# btnsm.net
KiCad netlist of a schematic drawn in EAGLE
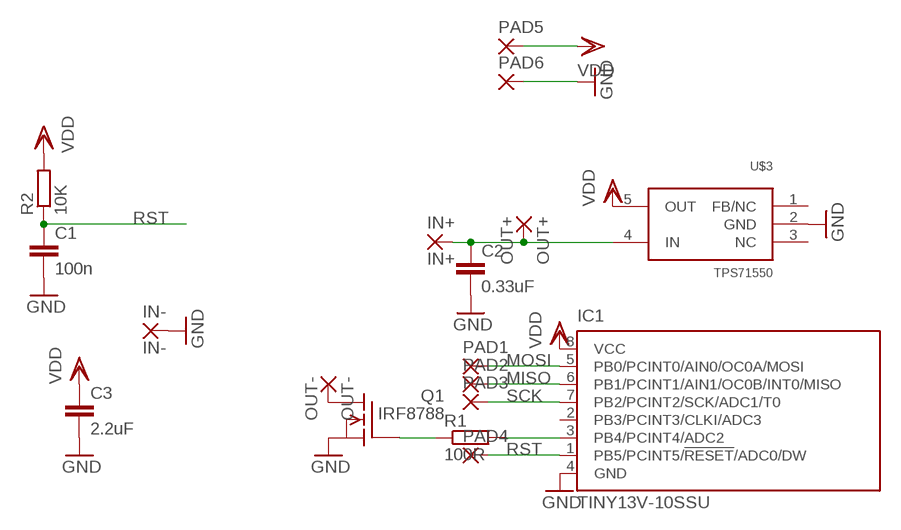
[diagram p0: schematic, sheet 1]

(export (version "E")
  (design (tool "Eeschema 10.0.6"))
  (components
    (comp (ref "C1")
      (value "100n")
      (footprint "eagle-import:C0603")
      (libsource (lib "eagle-import") (part "C-EUC0603"))
    )
    (comp (ref "C2")
      (value "0.33uF")
      (footprint "eagle-import:C0603")
      (libsource (lib "eagle-import") (part "C-EUC0603"))
    )
    (comp (ref "C3")
      (value "2.2uF")
      (footprint "eagle-import:C0603")
      (libsource (lib "eagle-import") (part "C-EUC0603"))
    )
    (comp (ref "IC1")
      (value "TINY13V-10SSU")
      (footprint "eagle-import:8S1")
      (fields (field (name "MPN") "ATTINY13V-10SSU"))
      (libsource (lib "eagle-import") (part "TINY13SSUV-10"))
    )
    (comp (ref "IN+")
      (value "IN+")
      (footprint "eagle-import:SMD2,54-5,08")
      (libsource (lib "eagle-import") (part "SMD5"))
    )
    (comp (ref "IN-")
      (value "IN-")
      (footprint "eagle-import:SMD2,54-5,08")
      (libsource (lib "eagle-import") (part "SMD5"))
    )
    (comp (ref "OUT+")
      (value "OUT+")
      (footprint "eagle-import:SMD2,54-5,08")
      (libsource (lib "eagle-import") (part "SMD5"))
    )
    (comp (ref "OUT-")
      (value "OUT-")
      (footprint "eagle-import:SMD2,54-5,08")
      (libsource (lib "eagle-import") (part "SMD5"))
    )
    (comp (ref "PAD1")
      (value "1,6/0,9")
      (footprint "eagle-import:1,6_0,9")
      (libsource (lib "eagle-import") (part "1,6/0,9"))
    )
    (comp (ref "PAD2")
      (value "1,6/0,9")
      (footprint "eagle-import:1,6_0,9")
      (libsource (lib "eagle-import") (part "1,6/0,9"))
    )
    (comp (ref "PAD3")
      (value "1,6/0,9")
      (footprint "eagle-import:1,6_0,9")
      (libsource (lib "eagle-import") (part "1,6/0,9"))
    )
    (comp (ref "PAD4")
      (value "1,6/0,9")
      (footprint "eagle-import:1,6_0,9")
      (libsource (lib "eagle-import") (part "1,6/0,9"))
    )
    (comp (ref "PAD5")
      (value "1,6/0,9")
      (footprint "eagle-import:1,6_0,9")
      (libsource (lib "eagle-import") (part "1,6/0,9"))
    )
    (comp (ref "PAD6")
      (value "1,6/0,9")
      (footprint "eagle-import:1,6_0,9")
      (libsource (lib "eagle-import") (part "1,6/0,9"))
    )
    (comp (ref "Q1")
      (value "IRF8788")
      (footprint "eagle-import:SO-8")
      (libsource (lib "eagle-import") (part "FDS5680"))
    )
    (comp (ref "R1")
      (value "100R")
      (footprint "eagle-import:R0402")
      (libsource (lib "eagle-import") (part "R-EU_R0402"))
    )
    (comp (ref "R2")
      (value "10K")
      (footprint "eagle-import:R0402")
      (libsource (lib "eagle-import") (part "R-EU_R0402"))
    )
    (comp (ref "U$3")
      (value "TPS71550")
      (footprint "eagle-import:SC70")
      (libsource (lib "eagle-import") (part "TPS715"))
    )
  )
  (nets
    (net (code "1") (name "/MISO") (class "Default")
      (node (ref "IC1") (pin "6") (pinfunction "PB1/PCINT1/AIN1/OC0B/INT0/MISO_6") (pintype "bidirectional"))
      (node (ref "PAD2") (pin "1") (pinfunction "P_1") (pintype "passive"))
    )
    (net (code "2") (name "/MOSI") (class "Default")
      (node (ref "IC1") (pin "5") (pinfunction "PB0/PCINT0/AIN0/OC0A/MOSI_5") (pintype "bidirectional"))
      (node (ref "PAD1") (pin "1") (pinfunction "P_1") (pintype "passive"))
    )
    (net (code "3") (name "/RST") (class "Default")
      (node (ref "C1") (pin "1") (pinfunction "1_1") (pintype "passive"))
      (node (ref "IC1") (pin "1") (pinfunction "PB5/PCINT5/~{RESET}/ADC0/DW_1") (pintype "bidirectional"))
      (node (ref "PAD4") (pin "1") (pinfunction "P_1") (pintype "passive"))
      (node (ref "R2") (pin "1") (pinfunction "1_1") (pintype "passive"))
    )
    (net (code "4") (name "/SCK") (class "Default")
      (node (ref "IC1") (pin "7") (pinfunction "PB2/PCINT2/SCK/ADC1/T0_7") (pintype "bidirectional"))
      (node (ref "PAD3") (pin "1") (pinfunction "P_1") (pintype "passive"))
    )
    (net (code "5") (name "GND") (class "Default")
      (node (ref "C1") (pin "2") (pinfunction "2_2") (pintype "passive"))
      (node (ref "C2") (pin "2") (pinfunction "2_2") (pintype "passive"))
      (node (ref "C3") (pin "2") (pinfunction "2_2") (pintype "passive"))
      (node (ref "IC1") (pin "4") (pinfunction "GND_4") (pintype "power_in"))
      (node (ref "IN-") (pin "1") (pinfunction "P_1") (pintype "passive"))
      (node (ref "PAD6") (pin "1") (pinfunction "P_1") (pintype "passive"))
      (node (ref "Q1") (pin "1") (pinfunction "S_1") (pintype "passive"))
      (node (ref "Q1") (pin "2") (pinfunction "S_2") (pintype "passive"))
      (node (ref "Q1") (pin "3") (pinfunction "S_3") (pintype "passive"))
      (node (ref "U$3") (pin "2") (pinfunction "GND_2") (pintype "bidirectional"))
    )
    (net (code "6") (name "Net-(IC1-PB4{slash}PCINT4{slash}ADC2)") (class "Default")
      (node (ref "IC1") (pin "3") (pinfunction "PB4/PCINT4/ADC2_3") (pintype "bidirectional"))
      (node (ref "R1") (pin "2") (pinfunction "2_2") (pintype "passive"))
    )
    (net (code "7") (name "Net-(IN+-P)") (class "Default")
      (node (ref "C2") (pin "1") (pinfunction "1_1") (pintype "passive"))
      (node (ref "IN+") (pin "1") (pinfunction "P_1") (pintype "passive"))
      (node (ref "OUT+") (pin "1") (pinfunction "P_1") (pintype "passive"))
      (node (ref "U$3") (pin "4") (pinfunction "IN_4") (pintype "bidirectional"))
    )
    (net (code "8") (name "Net-(OUT--P)") (class "Default")
      (node (ref "OUT-") (pin "1") (pinfunction "P_1") (pintype "passive"))
      (node (ref "Q1") (pin "5") (pinfunction "D_5") (pintype "passive"))
      (node (ref "Q1") (pin "6") (pinfunction "D_6") (pintype "passive"))
      (node (ref "Q1") (pin "7") (pinfunction "D_7") (pintype "passive"))
      (node (ref "Q1") (pin "8") (pinfunction "D_8") (pintype "passive"))
    )
    (net (code "9") (name "Net-(Q1-G)") (class "Default")
      (node (ref "Q1") (pin "4") (pinfunction "G_4") (pintype "passive"))
      (node (ref "R1") (pin "1") (pinfunction "1_1") (pintype "passive"))
    )
    (net (code "10") (name "VDD") (class "Default")
      (node (ref "C3") (pin "1") (pinfunction "1_1") (pintype "passive"))
      (node (ref "IC1") (pin "8") (pinfunction "VCC_8") (pintype "power_in"))
      (node (ref "PAD5") (pin "1") (pinfunction "P_1") (pintype "passive"))
      (node (ref "R2") (pin "2") (pinfunction "2_2") (pintype "passive"))
      (node (ref "U$3") (pin "5") (pinfunction "OUT_5") (pintype "bidirectional"))
    )
    (net (code "11") (name "unconnected-(IC1-PB3{slash}PCINT3{slash}CLKI{slash}ADC3-Pad2)") (class "Default")
      (node (ref "IC1") (pin "2") (pinfunction "PB3/PCINT3/CLKI/ADC3_2") (pintype "bidirectional"))
    )
    (net (code "12") (name "unconnected-(U$3-FB{slash}NC-Pad1)") (class "Default")
      (node (ref "U$3") (pin "1") (pinfunction "FB/NC_1") (pintype "bidirectional"))
    )
    (net (code "13") (name "unconnected-(U$3-NC-Pad3)") (class "Default")
      (node (ref "U$3") (pin "3") (pinfunction "NC_3") (pintype "bidirectional"))
    )
  )
)
